# Sheet1.net
KiCad netlist of a schematic drawn in Altium Designer
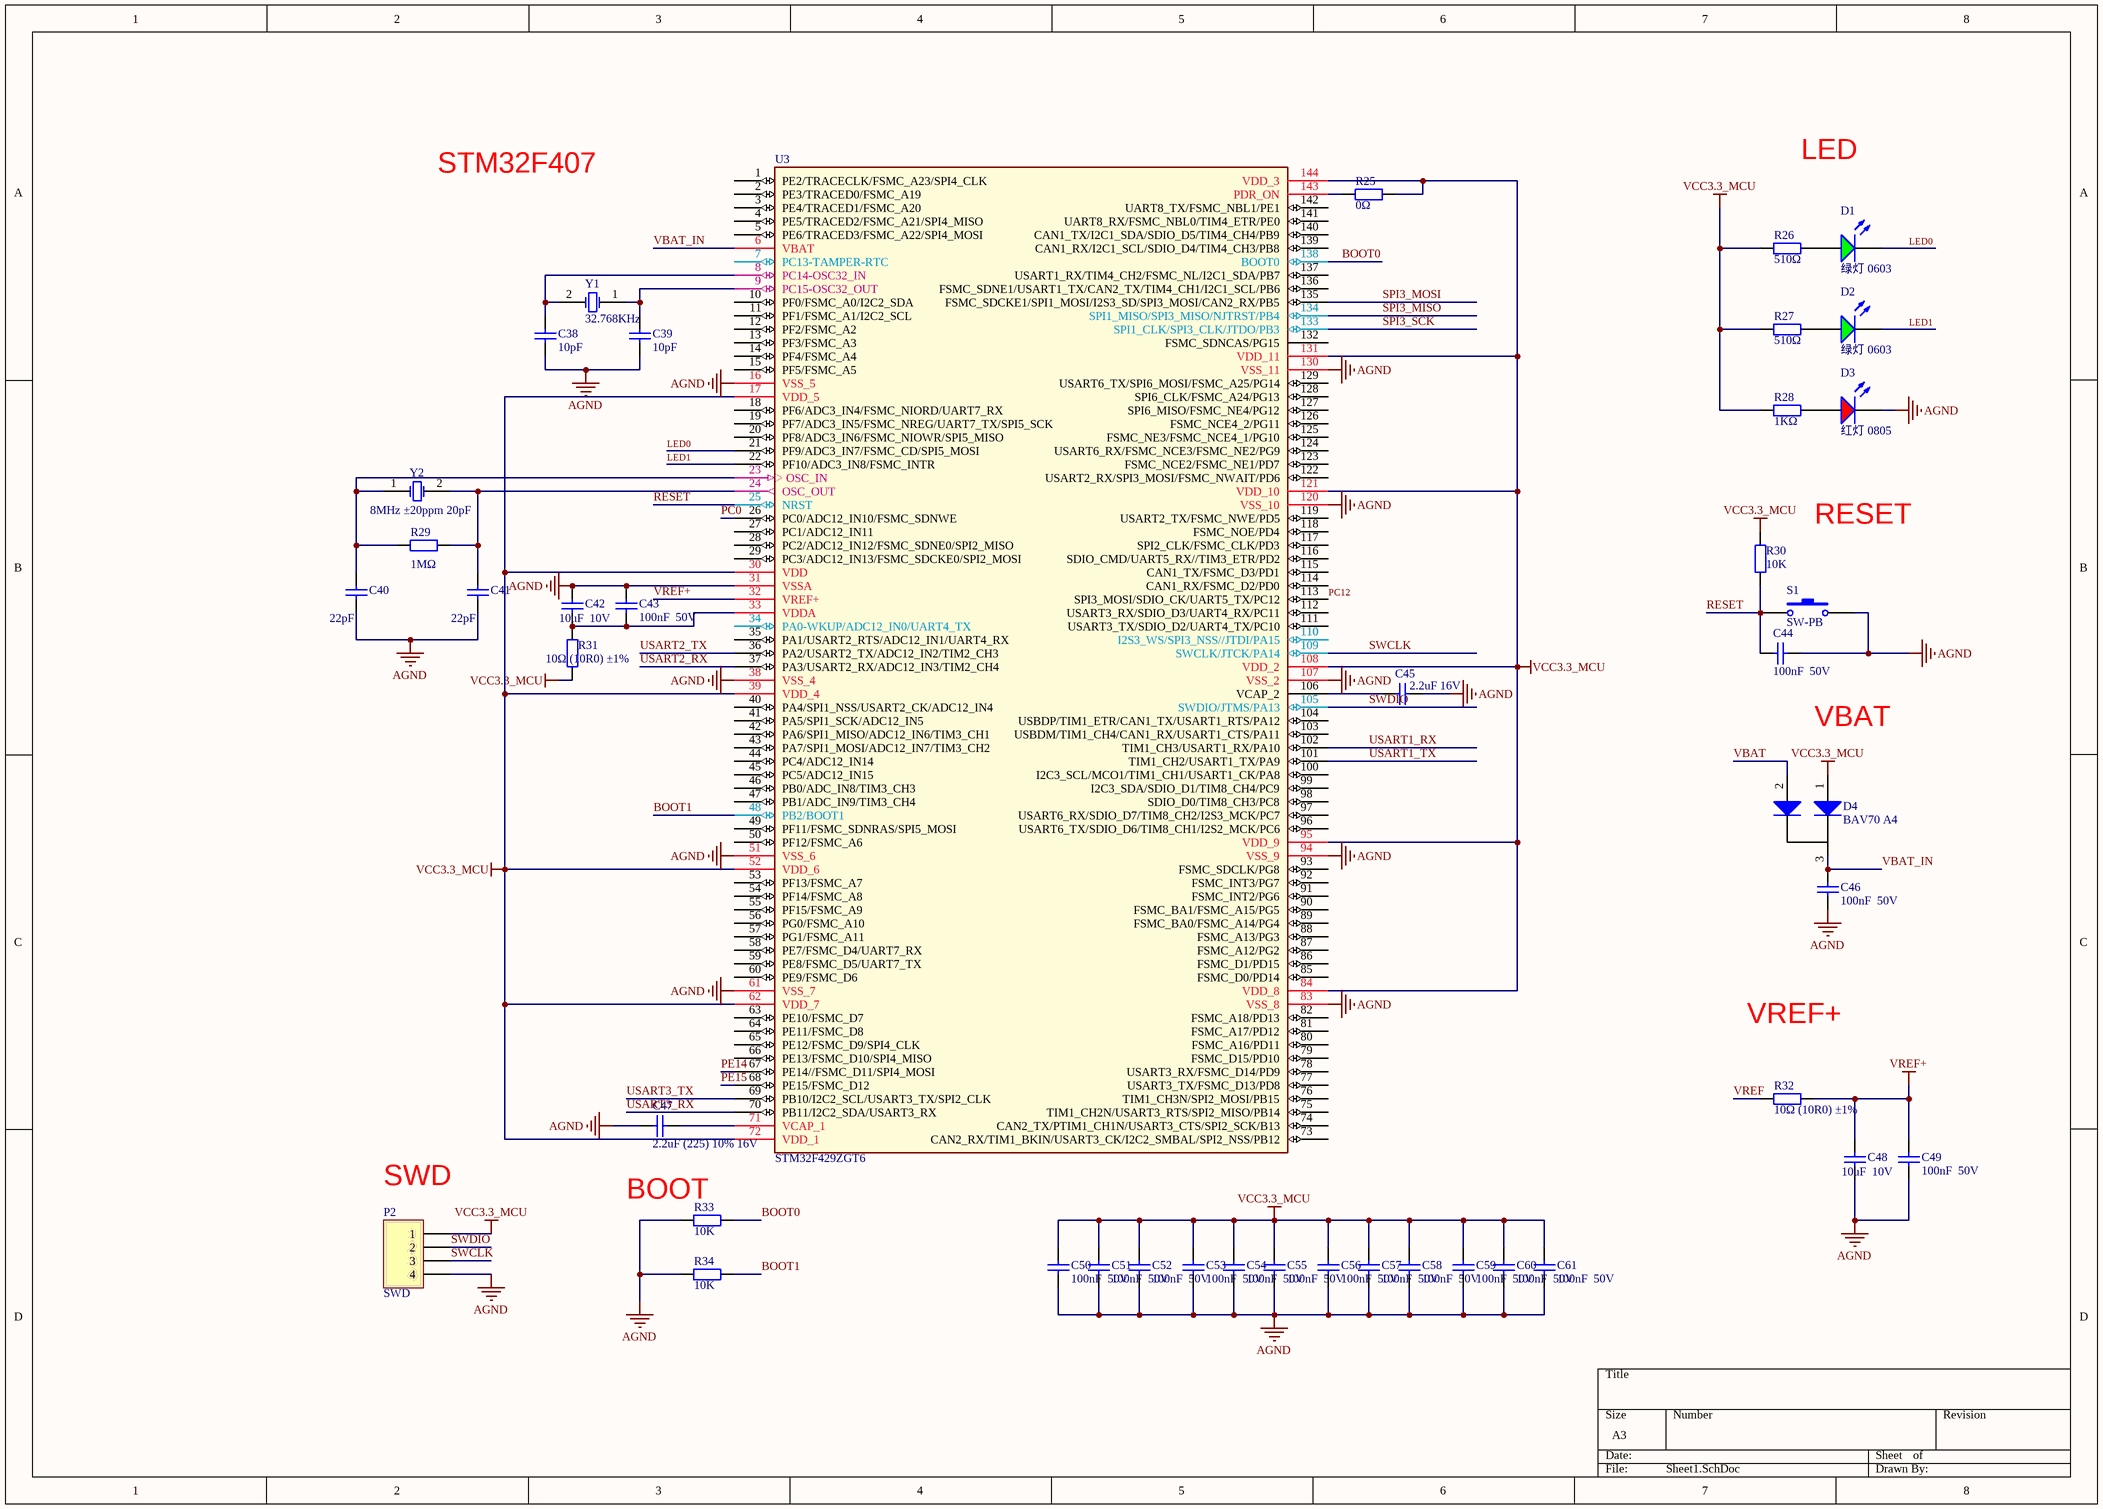
[diagram p0: Sheet1.SchDoc]

(export (version "E")
  (design (tool "Eeschema 10.0.6"))
  (components
    (comp (ref "C38")
      (value "10pF")
      (footprint "0603_C")
      (description "贴片电容")
      (libsource (lib "Miscellaneous Devices LC") (part "0603 10pF (100) 5% 50V"))
    )
    (comp (ref "C39")
      (value "10pF")
      (footprint "0603_C")
      (description "贴片电容")
      (libsource (lib "Miscellaneous Devices LC") (part "0603 10pF (100) 5% 50V"))
    )
    (comp (ref "C40")
      (value "22pF")
      (footprint "0603_C")
      (description "贴片电容")
      (libsource (lib "Miscellaneous Devices LC") (part "0603 22pF (220) 5% 50V"))
    )
    (comp (ref "C41")
      (value "22pF")
      (footprint "0603_C")
      (description "贴片电容")
      (libsource (lib "Miscellaneous Devices LC") (part "0603 22pF (220) 5% 50V"))
    )
    (comp (ref "C42")
      (value "10uF  10V")
      (footprint "0603_C")
      (description "贴片电容")
      (libsource (lib "Miscellaneous Devices LC") (part "0603 10uF (106) 10% 10V"))
    )
    (comp (ref "C43")
      (value "100nF  50V")
      (footprint "0603_C")
      (description "贴片电容")
      (libsource (lib "Miscellaneous Devices LC") (part "0603 100nF (104) 10% 50V"))
    )
    (comp (ref "C44")
      (value "100nF  50V")
      (footprint "0603_C")
      (description "贴片电容")
      (libsource (lib "Miscellaneous Devices LC") (part "0603 100nF (104) 10% 50V"))
    )
    (comp (ref "C45")
      (value "2.2uF 16V")
      (footprint "0603_C")
      (description "贴片电容")
      (libsource (lib "Miscellaneous Devices LC") (part "0603 2.2uF (225) 10% 16V"))
    )
    (comp (ref "C46")
      (value "100nF  50V")
      (footprint "0603_C")
      (description "贴片电容")
      (libsource (lib "Miscellaneous Devices LC") (part "0603 100nF (104) 10% 50V"))
    )
    (comp (ref "C47")
      (value "2.2uF (225) 10% 16V")
      (footprint "0603_C")
      (description "贴片电容")
      (libsource (lib "Miscellaneous Devices LC") (part "0603 2.2uF (225) 10% 16V"))
    )
    (comp (ref "C48")
      (value "10uF  10V")
      (footprint "0603_C")
      (description "贴片电容")
      (libsource (lib "Miscellaneous Devices LC") (part "0603 10uF (106) 10% 10V"))
    )
    (comp (ref "C49")
      (value "100nF  50V")
      (footprint "0603_C")
      (description "贴片电容")
      (libsource (lib "Miscellaneous Devices LC") (part "0603 100nF (104) 10% 50V"))
    )
    (comp (ref "C50")
      (value "100nF  50V")
      (footprint "0603_C")
      (description "贴片电容")
      (libsource (lib "Miscellaneous Devices LC") (part "0603 100nF (104) 10% 50V"))
    )
    (comp (ref "C51")
      (value "100nF  50V")
      (footprint "0603_C")
      (description "贴片电容")
      (libsource (lib "Miscellaneous Devices LC") (part "0603 100nF (104) 10% 50V"))
    )
    (comp (ref "C52")
      (value "100nF  50V")
      (footprint "0603_C")
      (description "贴片电容")
      (libsource (lib "Miscellaneous Devices LC") (part "0603 100nF (104) 10% 50V"))
    )
    (comp (ref "C53")
      (value "100nF  50V")
      (footprint "0603_C")
      (description "贴片电容")
      (libsource (lib "Miscellaneous Devices LC") (part "0603 100nF (104) 10% 50V"))
    )
    (comp (ref "C54")
      (value "100nF  50V")
      (footprint "0603_C")
      (description "贴片电容")
      (libsource (lib "Miscellaneous Devices LC") (part "0603 100nF (104) 10% 50V"))
    )
    (comp (ref "C55")
      (value "100nF  50V")
      (footprint "0603_C")
      (description "贴片电容")
      (libsource (lib "Miscellaneous Devices LC") (part "0603 100nF (104) 10% 50V"))
    )
    (comp (ref "C56")
      (value "100nF  50V")
      (footprint "0603_C")
      (description "贴片电容")
      (libsource (lib "Miscellaneous Devices LC") (part "0603 100nF (104) 10% 50V"))
    )
    (comp (ref "C57")
      (value "100nF  50V")
      (footprint "0603_C")
      (description "贴片电容")
      (libsource (lib "Miscellaneous Devices LC") (part "0603 100nF (104) 10% 50V"))
    )
    (comp (ref "C58")
      (value "100nF  50V")
      (footprint "0603_C")
      (description "贴片电容")
      (libsource (lib "Miscellaneous Devices LC") (part "0603 100nF (104) 10% 50V"))
    )
    (comp (ref "C59")
      (value "100nF  50V")
      (footprint "0603_C")
      (description "贴片电容")
      (libsource (lib "Miscellaneous Devices LC") (part "0603 100nF (104) 10% 50V"))
    )
    (comp (ref "C60")
      (value "100nF  50V")
      (footprint "0603_C")
      (description "贴片电容")
      (libsource (lib "Miscellaneous Devices LC") (part "0603 100nF (104) 10% 50V"))
    )
    (comp (ref "C61")
      (value "100nF  50V")
      (footprint "0603_C")
      (description "贴片电容")
      (libsource (lib "Miscellaneous Devices LC") (part "0603 100nF (104) 10% 50V"))
    )
    (comp (ref "D1")
      (value "绿灯 0603")
      (footprint "0603_LED_S1")
      (description "发光二极管")
      (libsource (lib "Miscellaneous Devices LC") (part "0603 绿灯"))
    )
    (comp (ref "D2")
      (value "绿灯 0603")
      (footprint "0603_LED_S1")
      (description "发光二极管")
      (libsource (lib "Miscellaneous Devices LC") (part "0603 绿灯"))
    )
    (comp (ref "D3")
      (value "红灯 0805")
      (footprint "0805_LED_S1")
      (description "发光二极管")
      (libsource (lib "Miscellaneous Devices LC") (part "0805 红灯"))
    )
    (comp (ref "D4")
      (value "BAV70 A4")
      (footprint "SOT-23(SOT-23-3)")
      (description "开关二极管")
      (libsource (lib "Miscellaneous Devices LC") (part "SOT-23 BAV70 A4"))
    )
    (comp (ref "P2")
      (value "SWD")
      (footprint "HDR1X4")
      (description "Header, 4-Pin")
      (fields (field (name "PUBLISHER") "Altium Limited"))
      (libsource (lib "Miscellaneous Connectors") (part "Header 4"))
    )
    (comp (ref "R25")
      (value "0Ω")
      (footprint "0603_R")
      (description "贴片电阻")
      (libsource (lib "Miscellaneous Devices LC") (part "0603 0Ω (0R0) 1%"))
    )
    (comp (ref "R26")
      (value "510Ω")
      (footprint "0603_R")
      (description "贴片电阻")
      (libsource (lib "Miscellaneous Devices LC") (part "0603 510Ω (5100) 1%"))
    )
    (comp (ref "R27")
      (value "510Ω")
      (footprint "0603_R")
      (description "贴片电阻")
      (libsource (lib "Miscellaneous Devices LC") (part "0603 510Ω (5100) 1%"))
    )
    (comp (ref "R28")
      (value "1KΩ")
      (footprint "0603_R")
      (description "贴片电阻")
      (libsource (lib "Miscellaneous Devices LC") (part "0603 1KΩ (1001) 1%"))
    )
    (comp (ref "R29")
      (value "1MΩ")
      (footprint "0603_R")
      (description "贴片电阻")
      (libsource (lib "Miscellaneous Devices LC") (part "0603 1.2MΩ (1204) 1%"))
    )
    (comp (ref "R30")
      (value "10K")
      (footprint "0603_R")
      (description "贴片电阻")
      (libsource (lib "") (part "0603 10Ω (10R0) 1%_3"))
    )
    (comp (ref "R31")
      (value "10Ω (10R0) ±1%")
      (footprint "0603_R")
      (description "贴片电阻")
      (libsource (lib "") (part "0603 10Ω (10R0) 1%_2"))
    )
    (comp (ref "R32")
      (value "10Ω (10R0) ±1%")
      (footprint "0603_R")
      (description "贴片电阻")
      (libsource (lib "") (part "0603 10Ω (10R0) 1%_1"))
    )
    (comp (ref "R33")
      (value "10K")
      (footprint "0603_R")
      (description "贴片电阻")
      (libsource (lib "Miscellaneous Devices LC") (part "0603 10Ω (10R0) 1%"))
    )
    (comp (ref "R34")
      (value "10K")
      (footprint "0603_R")
      (description "贴片电阻")
      (libsource (lib "Miscellaneous Devices LC") (part "0603 10Ω (10R0) 1%"))
    )
    (comp (ref "S1")
      (value "SW-PB")
      (footprint "key_4.5*4.5*3.8")
      (description "Switch")
      (fields (field (name "PUBLISHER") "Altium Limited"))
      (libsource (lib "Miscellaneous Devices") (part "SW-PB"))
    )
    (comp (ref "U3")
      (value "STM32F429ZGT6")
      (footprint "LQFP-144_20x20x05P")
      (description "ARM")
      (libsource (lib "Miscellaneous Devices LC") (part "STM32F429ZGT6"))
    )
    (comp (ref "Y1")
      (value "32.768KHz")
      (footprint "SMD-5032_2P")
      (description "贴片晶振")
      (libsource (lib "Miscellaneous Devices LC") (part "SMD-5032_2P 8MHz 20ppm 20pF"))
    )
    (comp (ref "Y2")
      (value "8MHz ±20ppm 20pF")
      (footprint "SMD-5032_2P")
      (description "贴片晶振")
      (libsource (lib "Miscellaneous Devices LC") (part "SMD-5032_2P 8MHz 20ppm 20pF"))
    )
  )
  (nets
    (net (code "1") (name "/BOOT0") (class "Default")
      (node (ref "R33") (pin "2") (pinfunction "2_2") (pintype "passive"))
      (node (ref "U3") (pin "138") (pinfunction "BOOT0_138") (pintype "bidirectional"))
    )
    (net (code "2") (name "/BOOT1") (class "Default")
      (node (ref "R34") (pin "2") (pinfunction "2_2") (pintype "passive"))
      (node (ref "U3") (pin "48") (pinfunction "PB2/BOOT1_48") (pintype "bidirectional"))
    )
    (net (code "3") (name "/LED0") (class "Default")
      (node (ref "D1") (pin "K") (pinfunction "K_K") (pintype "passive"))
      (node (ref "U3") (pin "21") (pinfunction "PF9/ADC3_IN7/FSMC_CD/SPI5_MOSI_21") (pintype "bidirectional"))
    )
    (net (code "4") (name "/LED1") (class "Default")
      (node (ref "D2") (pin "K") (pinfunction "K_K") (pintype "passive"))
      (node (ref "U3") (pin "22") (pinfunction "PF10/ADC3_IN8/FSMC_INTR_22") (pintype "bidirectional"))
    )
    (net (code "5") (name "/PC0") (class "Default")
      (node (ref "U3") (pin "26") (pinfunction "PC0/ADC12_IN10/FSMC_SDNWE_26") (pintype "bidirectional"))
    )
    (net (code "6") (name "/PC12") (class "Default")
      (node (ref "U3") (pin "113") (pinfunction "SPI3_MOSI/SDIO_CK/UART5_TX/PC12_113") (pintype "bidirectional"))
    )
    (net (code "7") (name "/PE14") (class "Default")
      (node (ref "U3") (pin "67") (pinfunction "PE14//FSMC_D11/SPI4_MOSI_67") (pintype "bidirectional"))
    )
    (net (code "8") (name "/PE15") (class "Default")
      (node (ref "U3") (pin "68") (pinfunction "PE15/FSMC_D12_68") (pintype "bidirectional"))
    )
    (net (code "9") (name "/RESET") (class "Default")
      (node (ref "C44") (pin "2") (pinfunction "2_2") (pintype "passive"))
      (node (ref "R30") (pin "2") (pinfunction "2_2") (pintype "passive"))
      (node (ref "S1") (pin "1") (pinfunction "1_1") (pintype "passive"))
      (node (ref "U3") (pin "25") (pinfunction "NRST_25") (pintype "bidirectional"))
    )
    (net (code "10") (name "/SPI3_MISO") (class "Default")
      (node (ref "U3") (pin "134") (pinfunction "SPI1_MISO/SPI3_MISO/NJTRST/PB4_134") (pintype "bidirectional"))
    )
    (net (code "11") (name "/SPI3_MOSI") (class "Default")
      (node (ref "U3") (pin "135") (pinfunction "FSMC_SDCKE1/SPI1_MOSI/I2S3_SD/SPI3_MOSI/CAN2_RX/PB5_135") (pintype "bidirectional"))
    )
    (net (code "12") (name "/SPI3_SCK") (class "Default")
      (node (ref "U3") (pin "133") (pinfunction "SPI1_CLK/SPI3_CLK/JTDO/PB3_133") (pintype "bidirectional"))
    )
    (net (code "13") (name "/SWCLK") (class "Default")
      (node (ref "P2") (pin "3") (pinfunction "3_3") (pintype "passive"))
      (node (ref "U3") (pin "109") (pinfunction "SWCLK/JTCK/PA14_109") (pintype "bidirectional"))
    )
    (net (code "14") (name "/SWDIO") (class "Default")
      (node (ref "P2") (pin "2") (pinfunction "2_2") (pintype "passive"))
      (node (ref "U3") (pin "105") (pinfunction "SWDIO/JTMS/PA13_105") (pintype "bidirectional"))
    )
    (net (code "15") (name "/USART1_RX") (class "Default")
      (node (ref "U3") (pin "102") (pinfunction "TIM1_CH3/USART1_RX/PA10_102") (pintype "bidirectional"))
    )
    (net (code "16") (name "/USART1_TX") (class "Default")
      (node (ref "U3") (pin "101") (pinfunction "TIM1_CH2/USART1_TX/PA9_101") (pintype "bidirectional"))
    )
    (net (code "17") (name "/USART2_RX") (class "Default")
      (node (ref "U3") (pin "37") (pinfunction "PA3/USART2_RX/ADC12_IN3/TIM2_CH4_37") (pintype "bidirectional"))
    )
    (net (code "18") (name "/USART2_TX") (class "Default")
      (node (ref "U3") (pin "36") (pinfunction "PA2/USART2_TX/ADC12_IN2/TIM2_CH3_36") (pintype "bidirectional"))
    )
    (net (code "19") (name "/USART3_RX") (class "Default")
      (node (ref "U3") (pin "70") (pinfunction "PB11/I2C2_SDA/USART3_RX_70") (pintype "bidirectional"))
    )
    (net (code "20") (name "/USART3_TX") (class "Default")
      (node (ref "U3") (pin "69") (pinfunction "PB10/I2C2_SCL/USART3_TX/SPI2_CLK_69") (pintype "bidirectional"))
    )
    (net (code "21") (name "/VBAT") (class "Default")
      (node (ref "D4") (pin "2") (pinfunction "A_2") (pintype "passive"))
    )
    (net (code "22") (name "/VBAT_IN") (class "Default")
      (node (ref "C46") (pin "1") (pinfunction "1_1") (pintype "passive"))
      (node (ref "D4") (pin "3") (pinfunction "K_3") (pintype "passive"))
      (node (ref "U3") (pin "6") (pinfunction "VBAT_6") (pintype "power_in"))
    )
    (net (code "23") (name "/VREF") (class "Default")
      (node (ref "R32") (pin "2") (pinfunction "2_2") (pintype "passive"))
    )
    (net (code "24") (name "AGND") (class "Default")
      (node (ref "C38") (pin "1") (pinfunction "1_1") (pintype "passive"))
      (node (ref "C39") (pin "1") (pinfunction "1_1") (pintype "passive"))
      (node (ref "C40") (pin "1") (pinfunction "1_1") (pintype "passive"))
      (node (ref "C41") (pin "1") (pinfunction "1_1") (pintype "passive"))
      (node (ref "C42") (pin "2") (pinfunction "2_2") (pintype "passive"))
      (node (ref "C43") (pin "2") (pinfunction "2_2") (pintype "passive"))
      (node (ref "C44") (pin "1") (pinfunction "1_1") (pintype "passive"))
      (node (ref "C45") (pin "1") (pinfunction "1_1") (pintype "passive"))
      (node (ref "C46") (pin "2") (pinfunction "2_2") (pintype "passive"))
      (node (ref "C47") (pin "1") (pinfunction "1_1") (pintype "passive"))
      (node (ref "C48") (pin "1") (pinfunction "1_1") (pintype "passive"))
      (node (ref "C49") (pin "1") (pinfunction "1_1") (pintype "passive"))
      (node (ref "C50") (pin "1") (pinfunction "1_1") (pintype "passive"))
      (node (ref "C51") (pin "1") (pinfunction "1_1") (pintype "passive"))
      (node (ref "C52") (pin "1") (pinfunction "1_1") (pintype "passive"))
      (node (ref "C53") (pin "1") (pinfunction "1_1") (pintype "passive"))
      (node (ref "C54") (pin "1") (pinfunction "1_1") (pintype "passive"))
      (node (ref "C55") (pin "1") (pinfunction "1_1") (pintype "passive"))
      (node (ref "C56") (pin "1") (pinfunction "1_1") (pintype "passive"))
      (node (ref "C57") (pin "1") (pinfunction "1_1") (pintype "passive"))
      (node (ref "C58") (pin "1") (pinfunction "1_1") (pintype "passive"))
      (node (ref "C59") (pin "1") (pinfunction "1_1") (pintype "passive"))
      (node (ref "C60") (pin "1") (pinfunction "1_1") (pintype "passive"))
      (node (ref "C61") (pin "1") (pinfunction "1_1") (pintype "passive"))
      (node (ref "D3") (pin "K") (pinfunction "K_K") (pintype "passive"))
      (node (ref "P2") (pin "4") (pinfunction "4_4") (pintype "passive"))
      (node (ref "R33") (pin "1") (pinfunction "1_1") (pintype "passive"))
      (node (ref "R34") (pin "1") (pinfunction "1_1") (pintype "passive"))
      (node (ref "S1") (pin "2") (pinfunction "2_2") (pintype "passive"))
      (node (ref "U3") (pin "107") (pinfunction "VSS_2_107") (pintype "power_in"))
      (node (ref "U3") (pin "120") (pinfunction "VSS_10_120") (pintype "power_in"))
      (node (ref "U3") (pin "130") (pinfunction "VSS_11_130") (pintype "power_in"))
      (node (ref "U3") (pin "16") (pinfunction "VSS_5_16") (pintype "power_in"))
      (node (ref "U3") (pin "31") (pinfunction "VSSA_31") (pintype "power_in"))
      (node (ref "U3") (pin "38") (pinfunction "VSS_4_38") (pintype "power_in"))
      (node (ref "U3") (pin "51") (pinfunction "VSS_6_51") (pintype "power_in"))
      (node (ref "U3") (pin "61") (pinfunction "VSS_7_61") (pintype "power_in"))
      (node (ref "U3") (pin "83") (pinfunction "VSS_8_83") (pintype "power_in"))
      (node (ref "U3") (pin "94") (pinfunction "VSS_9_94") (pintype "power_in"))
    )
    (net (code "25") (name "Net-(D1-PadA)") (class "Default")
      (node (ref "D1") (pin "A") (pinfunction "A_A") (pintype "passive"))
      (node (ref "R26") (pin "2") (pinfunction "2_2") (pintype "passive"))
    )
    (net (code "26") (name "Net-(D2-PadA)") (class "Default")
      (node (ref "D2") (pin "A") (pinfunction "A_A") (pintype "passive"))
      (node (ref "R27") (pin "2") (pinfunction "2_2") (pintype "passive"))
    )
    (net (code "27") (name "Net-(D3-PadA)") (class "Default")
      (node (ref "D3") (pin "A") (pinfunction "A_A") (pintype "passive"))
      (node (ref "R28") (pin "2") (pinfunction "2_2") (pintype "passive"))
    )
    (net (code "28") (name "Net-(U3-OSC_IN)") (class "Default")
      (node (ref "C40") (pin "2") (pinfunction "2_2") (pintype "passive"))
      (node (ref "R29") (pin "1") (pinfunction "1_1") (pintype "passive"))
      (node (ref "U3") (pin "23") (pinfunction "OSC_IN_23") (pintype "input"))
      (node (ref "Y2") (pin "1") (pinfunction "OSC1_1") (pintype "passive"))
    )
    (net (code "29") (name "Net-(U3-OSC_OUT)") (class "Default")
      (node (ref "C41") (pin "2") (pinfunction "2_2") (pintype "passive"))
      (node (ref "R29") (pin "2") (pinfunction "2_2") (pintype "passive"))
      (node (ref "U3") (pin "24") (pinfunction "OSC_OUT_24") (pintype "output"))
      (node (ref "Y2") (pin "2") (pinfunction "OSC2_2") (pintype "passive"))
    )
    (net (code "30") (name "Net-(U3-PC14-OSC32_IN)") (class "Default")
      (node (ref "C38") (pin "2") (pinfunction "2_2") (pintype "passive"))
      (node (ref "U3") (pin "8") (pinfunction "PC14-OSC32_IN_8") (pintype "bidirectional"))
      (node (ref "Y1") (pin "2") (pinfunction "OSC2_2") (pintype "passive"))
    )
    (net (code "31") (name "Net-(U3-PC15-OSC32_OUT)") (class "Default")
      (node (ref "C39") (pin "2") (pinfunction "2_2") (pintype "passive"))
      (node (ref "U3") (pin "9") (pinfunction "PC15-OSC32_OUT_9") (pintype "bidirectional"))
      (node (ref "Y1") (pin "1") (pinfunction "OSC1_1") (pintype "passive"))
    )
    (net (code "32") (name "Net-(U3-PDR_ON)") (class "Default")
      (node (ref "R25") (pin "2") (pinfunction "2_2") (pintype "passive"))
      (node (ref "U3") (pin "143") (pinfunction "PDR_ON_143") (pintype "power_in"))
    )
    (net (code "33") (name "Net-(U3-VCAP_1)") (class "Default")
      (node (ref "C47") (pin "2") (pinfunction "2_2") (pintype "passive"))
      (node (ref "U3") (pin "71") (pinfunction "VCAP_1_71") (pintype "power_in"))
    )
    (net (code "34") (name "Net-(U3-VCAP_2)") (class "Default")
      (node (ref "C45") (pin "2") (pinfunction "2_2") (pintype "passive"))
      (node (ref "U3") (pin "106") (pinfunction "VCAP_2_106") (pintype "tri_state"))
    )
    (net (code "35") (name "Net-(U3-VDDA)") (class "Default")
      (node (ref "C42") (pin "1") (pinfunction "1_1") (pintype "passive"))
      (node (ref "C43") (pin "1") (pinfunction "1_1") (pintype "passive"))
      (node (ref "R31") (pin "2") (pinfunction "2_2") (pintype "passive"))
      (node (ref "U3") (pin "33") (pinfunction "VDDA_33") (pintype "power_in"))
    )
    (net (code "36") (name "VCC3.3_MCU") (class "Default")
      (node (ref "C50") (pin "2") (pinfunction "2_2") (pintype "passive"))
      (node (ref "C51") (pin "2") (pinfunction "2_2") (pintype "passive"))
      (node (ref "C52") (pin "2") (pinfunction "2_2") (pintype "passive"))
      (node (ref "C53") (pin "2") (pinfunction "2_2") (pintype "passive"))
      (node (ref "C54") (pin "2") (pinfunction "2_2") (pintype "passive"))
      (node (ref "C55") (pin "2") (pinfunction "2_2") (pintype "passive"))
      (node (ref "C56") (pin "2") (pinfunction "2_2") (pintype "passive"))
      (node (ref "C57") (pin "2") (pinfunction "2_2") (pintype "passive"))
      (node (ref "C58") (pin "2") (pinfunction "2_2") (pintype "passive"))
      (node (ref "C59") (pin "2") (pinfunction "2_2") (pintype "passive"))
      (node (ref "C60") (pin "2") (pinfunction "2_2") (pintype "passive"))
      (node (ref "C61") (pin "2") (pinfunction "2_2") (pintype "passive"))
      (node (ref "D4") (pin "1") (pinfunction "A_1") (pintype "passive"))
      (node (ref "P2") (pin "1") (pinfunction "1_1") (pintype "passive"))
      (node (ref "R25") (pin "1") (pinfunction "1_1") (pintype "passive"))
      (node (ref "R26") (pin "1") (pinfunction "1_1") (pintype "passive"))
      (node (ref "R27") (pin "1") (pinfunction "1_1") (pintype "passive"))
      (node (ref "R28") (pin "1") (pinfunction "1_1") (pintype "passive"))
      (node (ref "R30") (pin "1") (pinfunction "1_1") (pintype "passive"))
      (node (ref "R31") (pin "1") (pinfunction "1_1") (pintype "passive"))
      (node (ref "U3") (pin "108") (pinfunction "VDD_2_108") (pintype "power_in"))
      (node (ref "U3") (pin "121") (pinfunction "VDD_10_121") (pintype "power_in"))
      (node (ref "U3") (pin "131") (pinfunction "VDD_11_131") (pintype "power_in"))
      (node (ref "U3") (pin "144") (pinfunction "VDD_3_144") (pintype "power_in"))
      (node (ref "U3") (pin "17") (pinfunction "VDD_5_17") (pintype "power_in"))
      (node (ref "U3") (pin "30") (pinfunction "VDD_30") (pintype "power_in"))
      (node (ref "U3") (pin "39") (pinfunction "VDD_4_39") (pintype "power_in"))
      (node (ref "U3") (pin "52") (pinfunction "VDD_6_52") (pintype "power_in"))
      (node (ref "U3") (pin "62") (pinfunction "VDD_7_62") (pintype "power_in"))
      (node (ref "U3") (pin "72") (pinfunction "VDD_1_72") (pintype "power_in"))
      (node (ref "U3") (pin "84") (pinfunction "VDD_8_84") (pintype "power_in"))
      (node (ref "U3") (pin "95") (pinfunction "VDD_9_95") (pintype "power_in"))
    )
    (net (code "37") (name "VREF+") (class "Default")
      (node (ref "C48") (pin "2") (pinfunction "2_2") (pintype "passive"))
      (node (ref "C49") (pin "2") (pinfunction "2_2") (pintype "passive"))
      (node (ref "R32") (pin "1") (pinfunction "1_1") (pintype "passive"))
      (node (ref "U3") (pin "32") (pinfunction "VREF+_32") (pintype "power_in"))
    )
    (net (code "38") (name "unconnected-(U3-CAN1_RX{slash}FSMC_D2{slash}PD0-Pad114)") (class "Default")
      (node (ref "U3") (pin "114") (pinfunction "CAN1_RX/FSMC_D2/PD0_114") (pintype "bidirectional"))
    )
    (net (code "39") (name "unconnected-(U3-CAN1_RX{slash}I2C1_SCL{slash}SDIO_D4{slash}TIM4_CH3{slash}PB8-Pad139)") (class "Default")
      (node (ref "U3") (pin "139") (pinfunction "CAN1_RX/I2C1_SCL/SDIO_D4/TIM4_CH3/PB8_139") (pintype "bidirectional"))
    )
    (net (code "40") (name "unconnected-(U3-CAN1_TX{slash}FSMC_D3{slash}PD1-Pad115)") (class "Default")
      (node (ref "U3") (pin "115") (pinfunction "CAN1_TX/FSMC_D3/PD1_115") (pintype "bidirectional"))
    )
    (net (code "41") (name "unconnected-(U3-CAN1_TX{slash}I2C1_SDA{slash}SDIO_D5{slash}TIM4_CH4{slash}PB9-Pad140)") (class "Default")
      (node (ref "U3") (pin "140") (pinfunction "CAN1_TX/I2C1_SDA/SDIO_D5/TIM4_CH4/PB9_140") (pintype "bidirectional"))
    )
    (net (code "42") (name "unconnected-(U3-CAN2_RX{slash}TIM1_BKIN{slash}USART3_CK{slash}I2C2_SMBAL{slash}SPI2_NSS{slash}PB12-Pad73)") (class "Default")
      (node (ref "U3") (pin "73") (pinfunction "CAN2_RX/TIM1_BKIN/USART3_CK/I2C2_SMBAL/SPI2_NSS/PB12_73") (pintype "bidirectional"))
    )
    (net (code "43") (name "unconnected-(U3-CAN2_TX{slash}PTIM1_CH1N{slash}USART3_CTS{slash}SPI2_SCK{slash}B13-Pad74)") (class "Default")
      (node (ref "U3") (pin "74") (pinfunction "CAN2_TX/PTIM1_CH1N/USART3_CTS/SPI2_SCK/B13_74") (pintype "bidirectional"))
    )
    (net (code "44") (name "unconnected-(U3-FSMC_A12{slash}PG2-Pad87)") (class "Default")
      (node (ref "U3") (pin "87") (pinfunction "FSMC_A12/PG2_87") (pintype "bidirectional"))
    )
    (net (code "45") (name "unconnected-(U3-FSMC_A13{slash}PG3-Pad88)") (class "Default")
      (node (ref "U3") (pin "88") (pinfunction "FSMC_A13/PG3_88") (pintype "bidirectional"))
    )
    (net (code "46") (name "unconnected-(U3-FSMC_A16{slash}PD11-Pad80)") (class "Default")
      (node (ref "U3") (pin "80") (pinfunction "FSMC_A16/PD11_80") (pintype "bidirectional"))
    )
    (net (code "47") (name "unconnected-(U3-FSMC_A17{slash}PD12-Pad81)") (class "Default")
      (node (ref "U3") (pin "81") (pinfunction "FSMC_A17/PD12_81") (pintype "bidirectional"))
    )
    (net (code "48") (name "unconnected-(U3-FSMC_A18{slash}PD13-Pad82)") (class "Default")
      (node (ref "U3") (pin "82") (pinfunction "FSMC_A18/PD13_82") (pintype "bidirectional"))
    )
    (net (code "49") (name "unconnected-(U3-FSMC_BA0{slash}FSMC_A14{slash}PG4-Pad89)") (class "Default")
      (node (ref "U3") (pin "89") (pinfunction "FSMC_BA0/FSMC_A14/PG4_89") (pintype "bidirectional"))
    )
    (net (code "50") (name "unconnected-(U3-FSMC_BA1{slash}FSMC_A15{slash}PG5-Pad90)") (class "Default")
      (node (ref "U3") (pin "90") (pinfunction "FSMC_BA1/FSMC_A15/PG5_90") (pintype "bidirectional"))
    )
    (net (code "51") (name "unconnected-(U3-FSMC_D0{slash}PD14-Pad85)") (class "Default")
      (node (ref "U3") (pin "85") (pinfunction "FSMC_D0/PD14_85") (pintype "bidirectional"))
    )
    (net (code "52") (name "unconnected-(U3-FSMC_D1{slash}PD15-Pad86)") (class "Default")
      (node (ref "U3") (pin "86") (pinfunction "FSMC_D1/PD15_86") (pintype "bidirectional"))
    )
    (net (code "53") (name "unconnected-(U3-FSMC_D15{slash}PD10-Pad79)") (class "Default")
      (node (ref "U3") (pin "79") (pinfunction "FSMC_D15/PD10_79") (pintype "bidirectional"))
    )
    (net (code "54") (name "unconnected-(U3-FSMC_INT2{slash}PG6-Pad91)") (class "Default")
      (node (ref "U3") (pin "91") (pinfunction "FSMC_INT2/PG6_91") (pintype "bidirectional"))
    )
    (net (code "55") (name "unconnected-(U3-FSMC_INT3{slash}PG7-Pad92)") (class "Default")
      (node (ref "U3") (pin "92") (pinfunction "FSMC_INT3/PG7_92") (pintype "bidirectional"))
    )
    (net (code "56") (name "unconnected-(U3-FSMC_NCE2{slash}FSMC_NE1{slash}PD7-Pad123)") (class "Default")
      (node (ref "U3") (pin "123") (pinfunction "FSMC_NCE2/FSMC_NE1/PD7_123") (pintype "bidirectional"))
    )
    (net (code "57") (name "unconnected-(U3-FSMC_NCE4_2{slash}PG11-Pad126)") (class "Default")
      (node (ref "U3") (pin "126") (pinfunction "FSMC_NCE4_2/PG11_126") (pintype "bidirectional"))
    )
    (net (code "58") (name "unconnected-(U3-FSMC_NE3{slash}FSMC_NCE4_1{slash}PG10-Pad125)") (class "Default")
      (node (ref "U3") (pin "125") (pinfunction "FSMC_NE3/FSMC_NCE4_1/PG10_125") (pintype "bidirectional"))
    )
    (net (code "59") (name "unconnected-(U3-FSMC_NOE{slash}PD4-Pad118)") (class "Default")
      (node (ref "U3") (pin "118") (pinfunction "FSMC_NOE/PD4_118") (pintype "bidirectional"))
    )
    (net (code "60") (name "unconnected-(U3-FSMC_SDCLK{slash}PG8-Pad93)") (class "Default")
      (node (ref "U3") (pin "93") (pinfunction "FSMC_SDCLK/PG8_93") (pintype "bidirectional"))
    )
    (net (code "61") (name "unconnected-(U3-FSMC_SDNCAS{slash}PG15-Pad132)") (class "Default")
      (node (ref "U3") (pin "132") (pinfunction "FSMC_SDNCAS/PG15_132") (pintype "passive"))
    )
    (net (code "62") (name "unconnected-(U3-FSMC_SDNE1{slash}USART1_TX{slash}CAN2_TX{slash}TIM4_CH1{slash}I2C1_SCL{slash}PB6-Pad136)") (class "Default")
      (node (ref "U3") (pin "136") (pinfunction "FSMC_SDNE1/USART1_TX/CAN2_TX/TIM4_CH1/I2C1_SCL/PB6_136") (pintype "bidirectional"))
    )
    (net (code "63") (name "unconnected-(U3-I2C3_SCL{slash}MCO1{slash}TIM1_CH1{slash}USART1_CK{slash}PA8-Pad100)") (class "Default")
      (node (ref "U3") (pin "100") (pinfunction "I2C3_SCL/MCO1/TIM1_CH1/USART1_CK/PA8_100") (pintype "bidirectional"))
    )
    (net (code "64") (name "unconnected-(U3-I2C3_SDA{slash}SDIO_D1{slash}TIM8_CH4{slash}PC9-Pad99)") (class "Default")
      (node (ref "U3") (pin "99") (pinfunction "I2C3_SDA/SDIO_D1/TIM8_CH4/PC9_99") (pintype "bidirectional"))
    )
    (net (code "65") (name "unconnected-(U3-I2S3_WS{slash}SPI3_NSS{slash}{slash}JTDI{slash}PA15-Pad110)") (class "Default")
      (node (ref "U3") (pin "110") (pinfunction "I2S3_WS/SPI3_NSS//JTDI/PA15_110") (pintype "bidirectional"))
    )
    (net (code "66") (name "unconnected-(U3-PA0-WKUP{slash}ADC12_IN0{slash}UART4_TX-Pad34)") (class "Default")
      (node (ref "U3") (pin "34") (pinfunction "PA0-WKUP/ADC12_IN0/UART4_TX_34") (pintype "bidirectional"))
    )
    (net (code "67") (name "unconnected-(U3-PA1{slash}USART2_RTS{slash}ADC12_IN1{slash}UART4_RX-Pad35)") (class "Default")
      (node (ref "U3") (pin "35") (pinfunction "PA1/USART2_RTS/ADC12_IN1/UART4_RX_35") (pintype "bidirectional"))
    )
    (net (code "68") (name "unconnected-(U3-PA4{slash}SPI1_NSS{slash}USART2_CK{slash}ADC12_IN4-Pad40)") (class "Default")
      (node (ref "U3") (pin "40") (pinfunction "PA4/SPI1_NSS/USART2_CK/ADC12_IN4_40") (pintype "bidirectional"))
    )
    (net (code "69") (name "unconnected-(U3-PA5{slash}SPI1_SCK{slash}ADC12_IN5-Pad41)") (class "Default")
      (node (ref "U3") (pin "41") (pinfunction "PA5/SPI1_SCK/ADC12_IN5_41") (pintype "bidirectional"))
    )
    (net (code "70") (name "unconnected-(U3-PA6{slash}SPI1_MISO{slash}ADC12_IN6{slash}TIM3_CH1-Pad42)") (class "Default")
      (node (ref "U3") (pin "42") (pinfunction "PA6/SPI1_MISO/ADC12_IN6/TIM3_CH1_42") (pintype "bidirectional"))
    )
    (net (code "71") (name "unconnected-(U3-PA7{slash}SPI1_MOSI{slash}ADC12_IN7{slash}TIM3_CH2-Pad43)") (class "Default")
      (node (ref "U3") (pin "43") (pinfunction "PA7/SPI1_MOSI/ADC12_IN7/TIM3_CH2_43") (pintype "bidirectional"))
    )
    (net (code "72") (name "unconnected-(U3-PB0{slash}ADC_IN8{slash}TIM3_CH3-Pad46)") (class "Default")
      (node (ref "U3") (pin "46") (pinfunction "PB0/ADC_IN8/TIM3_CH3_46") (pintype "bidirectional"))
    )
    (net (code "73") (name "unconnected-(U3-PB1{slash}ADC_IN9{slash}TIM3_CH4-Pad47)") (class "Default")
      (node (ref "U3") (pin "47") (pinfunction "PB1/ADC_IN9/TIM3_CH4_47") (pintype "bidirectional"))
    )
    (net (code "74") (name "unconnected-(U3-PC1{slash}ADC12_IN11-Pad27)") (class "Default")
      (node (ref "U3") (pin "27") (pinfunction "PC1/ADC12_IN11_27") (pintype "bidirectional"))
    )
    (net (code "75") (name "unconnected-(U3-PC2{slash}ADC12_IN12{slash}FSMC_SDNE0{slash}SPI2_MISO-Pad28)") (class "Default")
      (node (ref "U3") (pin "28") (pinfunction "PC2/ADC12_IN12/FSMC_SDNE0/SPI2_MISO_28") (pintype "bidirectional"))
    )
    (net (code "76") (name "unconnected-(U3-PC3{slash}ADC12_IN13{slash}FSMC_SDCKE0{slash}SPI2_MOSI-Pad29)") (class "Default")
      (node (ref "U3") (pin "29") (pinfunction "PC3/ADC12_IN13/FSMC_SDCKE0/SPI2_MOSI_29") (pintype "bidirectional"))
    )
    (net (code "77") (name "unconnected-(U3-PC4{slash}ADC12_IN14-Pad44)") (class "Default")
      (node (ref "U3") (pin "44") (pinfunction "PC4/ADC12_IN14_44") (pintype "bidirectional"))
    )
    (net (code "78") (name "unconnected-(U3-PC5{slash}ADC12_IN15-Pad45)") (class "Default")
      (node (ref "U3") (pin "45") (pinfunction "PC5/ADC12_IN15_45") (pintype "bidirectional"))
    )
    (net (code "79") (name "unconnected-(U3-PC13-TAMPER-RTC-Pad7)") (class "Default")
      (node (ref "U3") (pin "7") (pinfunction "PC13-TAMPER-RTC_7") (pintype "bidirectional"))
    )
    (net (code "80") (name "unconnected-(U3-PE2{slash}TRACECLK{slash}FSMC_A23{slash}SPI4_CLK-Pad1)") (class "Default")
      (node (ref "U3") (pin "1") (pinfunction "PE2/TRACECLK/FSMC_A23/SPI4_CLK_1") (pintype "bidirectional"))
    )
    (net (code "81") (name "unconnected-(U3-PE3{slash}TRACED0{slash}FSMC_A19-Pad2)") (class "Default")
      (node (ref "U3") (pin "2") (pinfunction "PE3/TRACED0/FSMC_A19_2") (pintype "bidirectional"))
    )
    (net (code "82") (name "unconnected-(U3-PE4{slash}TRACED1{slash}FSMC_A20-Pad3)") (class "Default")
      (node (ref "U3") (pin "3") (pinfunction "PE4/TRACED1/FSMC_A20_3") (pintype "bidirectional"))
    )
    (net (code "83") (name "unconnected-(U3-PE5{slash}TRACED2{slash}FSMC_A21{slash}SPI4_MISO-Pad4)") (class "Default")
      (node (ref "U3") (pin "4") (pinfunction "PE5/TRACED2/FSMC_A21/SPI4_MISO_4") (pintype "bidirectional"))
    )
    (net (code "84") (name "unconnected-(U3-PE6{slash}TRACED3{slash}FSMC_A22{slash}SPI4_MOSI-Pad5)") (class "Default")
      (node (ref "U3") (pin "5") (pinfunction "PE6/TRACED3/FSMC_A22/SPI4_MOSI_5") (pintype "bidirectional"))
    )
    (net (code "85") (name "unconnected-(U3-PE7{slash}FSMC_D4{slash}UART7_RX-Pad58)") (class "Default")
      (node (ref "U3") (pin "58") (pinfunction "PE7/FSMC_D4/UART7_RX_58") (pintype "bidirectional"))
    )
    (net (code "86") (name "unconnected-(U3-PE8{slash}FSMC_D5{slash}UART7_TX-Pad59)") (class "Default")
      (node (ref "U3") (pin "59") (pinfunction "PE8/FSMC_D5/UART7_TX_59") (pintype "bidirectional"))
    )
    (net (code "87") (name "unconnected-(U3-PE9{slash}FSMC_D6-Pad60)") (class "Default")
      (node (ref "U3") (pin "60") (pinfunction "PE9/FSMC_D6_60") (pintype "bidirectional"))
    )
    (net (code "88") (name "unconnected-(U3-PE10{slash}FSMC_D7-Pad63)") (class "Default")
      (node (ref "U3") (pin "63") (pinfunction "PE10/FSMC_D7_63") (pintype "bidirectional"))
    )
    (net (code "89") (name "unconnected-(U3-PE11{slash}FSMC_D8-Pad64)") (class "Default")
      (node (ref "U3") (pin "64") (pinfunction "PE11/FSMC_D8_64") (pintype "bidirectional"))
    )
    (net (code "90") (name "unconnected-(U3-PE12{slash}FSMC_D9{slash}SPI4_CLK-Pad65)") (class "Default")
      (node (ref "U3") (pin "65") (pinfunction "PE12/FSMC_D9/SPI4_CLK_65") (pintype "bidirectional"))
    )
    (net (code "91") (name "unconnected-(U3-PE13{slash}FSMC_D10{slash}SPI4_MISO-Pad66)") (class "Default")
      (node (ref "U3") (pin "66") (pinfunction "PE13/FSMC_D10/SPI4_MISO_66") (pintype "bidirectional"))
    )
    (net (code "92") (name "unconnected-(U3-PF0{slash}FSMC_A0{slash}I2C2_SDA-Pad10)") (class "Default")
      (node (ref "U3") (pin "10") (pinfunction "PF0/FSMC_A0/I2C2_SDA_10") (pintype "bidirectional"))
    )
    (net (code "93") (name "unconnected-(U3-PF1{slash}FSMC_A1{slash}I2C2_SCL-Pad11)") (class "Default")
      (node (ref "U3") (pin "11") (pinfunction "PF1/FSMC_A1/I2C2_SCL_11") (pintype "bidirectional"))
    )
    (net (code "94") (name "unconnected-(U3-PF2{slash}FSMC_A2-Pad12)") (class "Default")
      (node (ref "U3") (pin "12") (pinfunction "PF2/FSMC_A2_12") (pintype "bidirectional"))
    )
    (net (code "95") (name "unconnected-(U3-PF3{slash}FSMC_A3-Pad13)") (class "Default")
      (node (ref "U3") (pin "13") (pinfunction "PF3/FSMC_A3_13") (pintype "bidirectional"))
    )
    (net (code "96") (name "unconnected-(U3-PF4{slash}FSMC_A4-Pad14)") (class "Default")
      (node (ref "U3") (pin "14") (pinfunction "PF4/FSMC_A4_14") (pintype "bidirectional"))
    )
    (net (code "97") (name "unconnected-(U3-PF5{slash}FSMC_A5-Pad15)") (class "Default")
      (node (ref "U3") (pin "15") (pinfunction "PF5/FSMC_A5_15") (pintype "bidirectional"))
    )
    (net (code "98") (name "unconnected-(U3-PF6{slash}ADC3_IN4{slash}FSMC_NIORD{slash}UART7_RX-Pad18)") (class "Default")
      (node (ref "U3") (pin "18") (pinfunction "PF6/ADC3_IN4/FSMC_NIORD/UART7_RX_18") (pintype "bidirectional"))
    )
    (net (code "99") (name "unconnected-(U3-PF7{slash}ADC3_IN5{slash}FSMC_NREG{slash}UART7_TX{slash}SPI5_SCK-Pad19)") (class "Default")
      (node (ref "U3") (pin "19") (pinfunction "PF7/ADC3_IN5/FSMC_NREG/UART7_TX/SPI5_SCK_19") (pintype "bidirectional"))
    )
    (net (code "100") (name "unconnected-(U3-PF8{slash}ADC3_IN6{slash}FSMC_NIOWR{slash}SPI5_MISO-Pad20)") (class "Default")
      (node (ref "U3") (pin "20") (pinfunction "PF8/ADC3_IN6/FSMC_NIOWR/SPI5_MISO_20") (pintype "bidirectional"))
    )
    (net (code "101") (name "unconnected-(U3-PF11{slash}FSMC_SDNRAS{slash}SPI5_MOSI-Pad49)") (class "Default")
      (node (ref "U3") (pin "49") (pinfunction "PF11/FSMC_SDNRAS/SPI5_MOSI_49") (pintype "bidirectional"))
    )
    (net (code "102") (name "unconnected-(U3-PF12{slash}FSMC_A6-Pad50)") (class "Default")
      (node (ref "U3") (pin "50") (pinfunction "PF12/FSMC_A6_50") (pintype "bidirectional"))
    )
    (net (code "103") (name "unconnected-(U3-PF13{slash}FSMC_A7-Pad53)") (class "Default")
      (node (ref "U3") (pin "53") (pinfunction "PF13/FSMC_A7_53") (pintype "bidirectional"))
    )
    (net (code "104") (name "unconnected-(U3-PF14{slash}FSMC_A8-Pad54)") (class "Default")
      (node (ref "U3") (pin "54") (pinfunction "PF14/FSMC_A8_54") (pintype "bidirectional"))
    )
    (net (code "105") (name "unconnected-(U3-PF15{slash}FSMC_A9-Pad55)") (class "Default")
      (node (ref "U3") (pin "55") (pinfunction "PF15/FSMC_A9_55") (pintype "bidirectional"))
    )
    (net (code "106") (name "unconnected-(U3-PG0{slash}FSMC_A10-Pad56)") (class "Default")
      (node (ref "U3") (pin "56") (pinfunction "PG0/FSMC_A10_56") (pintype "bidirectional"))
    )
    (net (code "107") (name "unconnected-(U3-PG1{slash}FSMC_A11-Pad57)") (class "Default")
      (node (ref "U3") (pin "57") (pinfunction "PG1/FSMC_A11_57") (pintype "bidirectional"))
    )
    (net (code "108") (name "unconnected-(U3-SDIO_CMD{slash}UART5_RX{slash}{slash}TIM3_ETR{slash}PD2-Pad116)") (class "Default")
      (node (ref "U3") (pin "116") (pinfunction "SDIO_CMD/UART5_RX//TIM3_ETR/PD2_116") (pintype "bidirectional"))
    )
    (net (code "109") (name "unconnected-(U3-SDIO_D0{slash}TIM8_CH3{slash}PC8-Pad98)") (class "Default")
      (node (ref "U3") (pin "98") (pinfunction "SDIO_D0/TIM8_CH3/PC8_98") (pintype "bidirectional"))
    )
    (net (code "110") (name "unconnected-(U3-SPI2_CLK{slash}FSMC_CLK{slash}PD3-Pad117)") (class "Default")
      (node (ref "U3") (pin "117") (pinfunction "SPI2_CLK/FSMC_CLK/PD3_117") (pintype "bidirectional"))
    )
    (net (code "111") (name "unconnected-(U3-SPI6_CLK{slash}FSMC_A24{slash}PG13-Pad128)") (class "Default")
      (node (ref "U3") (pin "128") (pinfunction "SPI6_CLK/FSMC_A24/PG13_128") (pintype "bidirectional"))
    )
    (net (code "112") (name "unconnected-(U3-SPI6_MISO{slash}FSMC_NE4{slash}PG12-Pad127)") (class "Default")
      (node (ref "U3") (pin "127") (pinfunction "SPI6_MISO/FSMC_NE4/PG12_127") (pintype "bidirectional"))
    )
    (net (code "113") (name "unconnected-(U3-TIM1_CH2N{slash}USART3_RTS{slash}SPI2_MISO{slash}PB14-Pad75)") (class "Default")
      (node (ref "U3") (pin "75") (pinfunction "TIM1_CH2N/USART3_RTS/SPI2_MISO/PB14_75") (pintype "bidirectional"))
    )
    (net (code "114") (name "unconnected-(U3-TIM1_CH3N{slash}SPI2_MOSI{slash}PB15-Pad76)") (class "Default")
      (node (ref "U3") (pin "76") (pinfunction "TIM1_CH3N/SPI2_MOSI/PB15_76") (pintype "bidirectional"))
    )
    (net (code "115") (name "unconnected-(U3-UART8_RX{slash}FSMC_NBL0{slash}TIM4_ETR{slash}PE0-Pad141)") (class "Default")
      (node (ref "U3") (pin "141") (pinfunction "UART8_RX/FSMC_NBL0/TIM4_ETR/PE0_141") (pintype "bidirectional"))
    )
    (net (code "116") (name "unconnected-(U3-UART8_TX{slash}FSMC_NBL1{slash}PE1-Pad142)") (class "Default")
      (node (ref "U3") (pin "142") (pinfunction "UART8_TX/FSMC_NBL1/PE1_142") (pintype "bidirectional"))
    )
    (net (code "117") (name "unconnected-(U3-USART1_RX{slash}TIM4_CH2{slash}FSMC_NL{slash}I2C1_SDA{slash}PB7-Pad137)") (class "Default")
      (node (ref "U3") (pin "137") (pinfunction "USART1_RX/TIM4_CH2/FSMC_NL/I2C1_SDA/PB7_137") (pintype "bidirectional"))
    )
    (net (code "118") (name "unconnected-(U3-USART2_RX{slash}SPI3_MOSI{slash}FSMC_NWAIT{slash}PD6-Pad122)") (class "Default")
      (node (ref "U3") (pin "122") (pinfunction "USART2_RX/SPI3_MOSI/FSMC_NWAIT/PD6_122") (pintype "bidirectional"))
    )
    (net (code "119") (name "unconnected-(U3-USART2_TX{slash}FSMC_NWE{slash}PD5-Pad119)") (class "Default")
      (node (ref "U3") (pin "119") (pinfunction "USART2_TX/FSMC_NWE/PD5_119") (pintype "bidirectional"))
    )
    (net (code "120") (name "unconnected-(U3-USART3_RX{slash}FSMC_D14{slash}PD9-Pad78)") (class "Default")
      (node (ref "U3") (pin "78") (pinfunction "USART3_RX/FSMC_D14/PD9_78") (pintype "bidirectional"))
    )
    (net (code "121") (name "unconnected-(U3-USART3_RX{slash}SDIO_D3{slash}UART4_RX{slash}PC11-Pad112)") (class "Default")
      (node (ref "U3") (pin "112") (pinfunction "USART3_RX/SDIO_D3/UART4_RX/PC11_112") (pintype "bidirectional"))
    )
    (net (code "122") (name "unconnected-(U3-USART3_TX{slash}FSMC_D13{slash}PD8-Pad77)") (class "Default")
      (node (ref "U3") (pin "77") (pinfunction "USART3_TX/FSMC_D13/PD8_77") (pintype "bidirectional"))
    )
    (net (code "123") (name "unconnected-(U3-USART3_TX{slash}SDIO_D2{slash}UART4_TX{slash}PC10-Pad111)") (class "Default")
      (node (ref "U3") (pin "111") (pinfunction "USART3_TX/SDIO_D2/UART4_TX/PC10_111") (pintype "bidirectional"))
    )
    (net (code "124") (name "unconnected-(U3-USART6_RX{slash}FSMC_NCE3{slash}FSMC_NE2{slash}PG9-Pad124)") (class "Default")
      (node (ref "U3") (pin "124") (pinfunction "USART6_RX/FSMC_NCE3/FSMC_NE2/PG9_124") (pintype "bidirectional"))
    )
    (net (code "125") (name "unconnected-(U3-USART6_RX{slash}SDIO_D7{slash}TIM8_CH2{slash}I2S3_MCK{slash}PC7-Pad97)") (class "Default")
      (node (ref "U3") (pin "97") (pinfunction "USART6_RX/SDIO_D7/TIM8_CH2/I2S3_MCK/PC7_97") (pintype "bidirectional"))
    )
    (net (code "126") (name "unconnected-(U3-USART6_TX{slash}SDIO_D6{slash}TIM8_CH1{slash}I2S2_MCK{slash}PC6-Pad96)") (class "Default")
      (node (ref "U3") (pin "96") (pinfunction "USART6_TX/SDIO_D6/TIM8_CH1/I2S2_MCK/PC6_96") (pintype "bidirectional"))
    )
    (net (code "127") (name "unconnected-(U3-USART6_TX{slash}SPI6_MOSI{slash}FSMC_A25{slash}PG14-Pad129)") (class "Default")
      (node (ref "U3") (pin "129") (pinfunction "USART6_TX/SPI6_MOSI/FSMC_A25/PG14_129") (pintype "bidirectional"))
    )
    (net (code "128") (name "unconnected-(U3-USBDM{slash}TIM1_CH4{slash}CAN1_RX{slash}USART1_CTS{slash}PA11-Pad103)") (class "Default")
      (node (ref "U3") (pin "103") (pinfunction "USBDM/TIM1_CH4/CAN1_RX/USART1_CTS/PA11_103") (pintype "bidirectional"))
    )
    (net (code "129") (name "unconnected-(U3-USBDP{slash}TIM1_ETR{slash}CAN1_TX{slash}USART1_RTS{slash}PA12-Pad104)") (class "Default")
      (node (ref "U3") (pin "104") (pinfunction "USBDP/TIM1_ETR/CAN1_TX/USART1_RTS/PA12_104") (pintype "bidirectional"))
    )
  )
)
